# EMU.net
KiCad netlist of a schematic drawn in Altium Designer
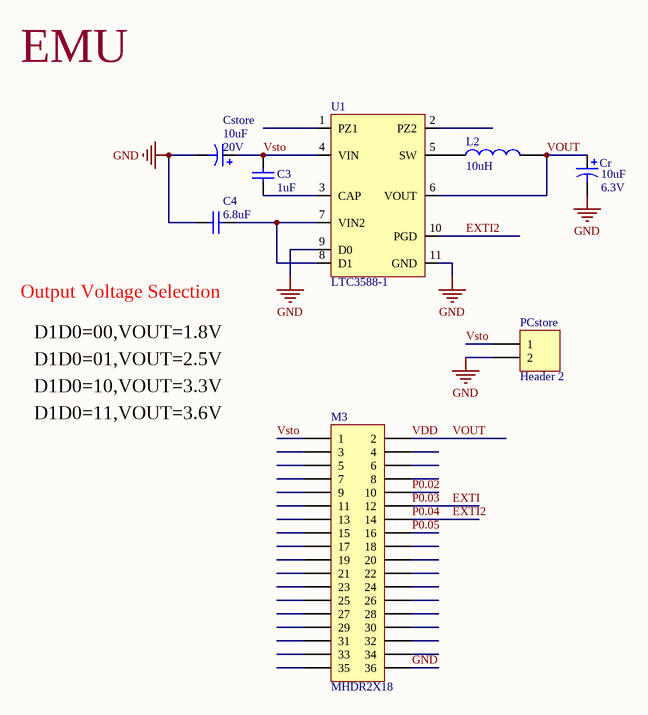
[diagram p0: EMU.SchDoc]

(export (version "E")
  (design (tool "Eeschema 10.0.6"))
  (components
    (comp (ref "C3")
      (value "1uF")
      (footprint "6-0805_N")
      (description "Capacitor")
      (fields (field (name "Comment") "CAP") (field (name "PUBLISHER") "Altium Limited"))
      (libsource (lib "Harry_PCBLib") (part "Cap"))
    )
    (comp (ref "C4")
      (value "6.8uF")
      (footprint "6-0805_N")
      (description "Capacitor")
      (fields (field (name "Comment") "CAP") (field (name "PUBLISHER") "Altium Limited"))
      (libsource (lib "Harry_PCBLib") (part "Cap"))
    )
    (comp (ref "Cr")
      (value "6.3V")
      (footprint "3216[1206]")
      (description "Polarized Capacitor (Radial)")
      (fields (field (name "ALTIUM_VALUE") "10uF") (field (name "PUBLISHER") "Altium Limited"))
      (libsource (lib "Miscellaneous Devices") (part "Cap Pol1"))
    )
    (comp (ref "Cstore")
      (value "10uF")
      (footprint "钽电容")
      (description "Polarized Capacitor (Radial)")
      (fields
        (field (name "NOMINAL VOLTAGE") "20V")
        (field (name "Comment") "Cap Pol1")
        (field (name "PUBLISHER") "Altium Limited")
      )
      (libsource (lib "Miscellaneous Devices") (part "Cap Pol1"))
    )
    (comp (ref "L2") (value "10uH") (footprint "1812") (libsource (lib "Harry_PCBLib") (part "INDUCTOR")))
    (comp (ref "M3")
      (value "MHDR2X18")
      (footprint "header:module9x4")
      (description "Header, 18-Pin, Dual row")
      (fields (field (name "PUBLISHER") "Altium Limited"))
      (libsource (lib "Miscellaneous Connectors") (part "MHDR2X18"))
    )
    (comp (ref "PCstore")
      (value "Header 2")
      (footprint "HDR1X2")
      (description "Header, 2-Pin")
      (fields (field (name "PUBLISHER") "Altium Limited"))
      (libsource (lib "Miscellaneous Connectors") (part "Header 2"))
    )
    (comp (ref "U1")
      (value "LTC3588-1")
      (footprint "LTC 3588-1")
      (description "Nanopower energy harvesting power supply")
      (libsource (lib "Self-power SSHI") (part "LTC3588-1"))
    )
  )
  (nets
    (net (code "1") (name "/EXTI") (class "Default")
      (node (ref "M3") (pin "12") (pinfunction "12_12") (pintype "passive"))
    )
    (net (code "2") (name "/EXTI2") (class "Default")
      (node (ref "M3") (pin "14") (pinfunction "14_14") (pintype "passive"))
      (node (ref "U1") (pin "10") (pinfunction "PGD_10") (pintype "passive"))
    )
    (net (code "3") (name "/P0.02") (class "Default")
      (node (ref "M3") (pin "10") (pinfunction "10_10") (pintype "passive"))
    )
    (net (code "4") (name "/P0.05") (class "Default")
      (node (ref "M3") (pin "16") (pinfunction "16_16") (pintype "passive"))
    )
    (net (code "5") (name "/VDD") (class "Default")
      (node (ref "Cr") (pin "1") (pinfunction "1_1") (pintype "passive"))
      (node (ref "L2") (pin "2") (pinfunction "2_2") (pintype "passive"))
      (node (ref "M3") (pin "2") (pinfunction "2_2") (pintype "passive"))
      (node (ref "U1") (pin "6") (pinfunction "VOUT_6") (pintype "passive"))
    )
    (net (code "6") (name "/Vsto") (class "Default")
      (node (ref "C3") (pin "2") (pinfunction "2_2") (pintype "passive"))
      (node (ref "Cstore") (pin "1") (pinfunction "1_1") (pintype "passive"))
      (node (ref "M3") (pin "1") (pinfunction "1_1") (pintype "passive"))
      (node (ref "PCstore") (pin "1") (pinfunction "1_1") (pintype "passive"))
      (node (ref "U1") (pin "4") (pinfunction "VIN_4") (pintype "passive"))
    )
    (net (code "7") (name "GND") (class "Default")
      (node (ref "C4") (pin "2") (pinfunction "2_2") (pintype "passive"))
      (node (ref "Cr") (pin "2") (pinfunction "2_2") (pintype "passive"))
      (node (ref "Cstore") (pin "2") (pinfunction "2_2") (pintype "passive"))
      (node (ref "M3") (pin "36") (pinfunction "36_36") (pintype "passive"))
      (node (ref "PCstore") (pin "2") (pinfunction "2_2") (pintype "passive"))
      (node (ref "U1") (pin "11") (pinfunction "GND_11") (pintype "passive"))
      (node (ref "U1") (pin "9") (pinfunction "D0_9") (pintype "passive"))
    )
    (net (code "8") (name "Net-(U1-CAP)") (class "Default")
      (node (ref "C3") (pin "1") (pinfunction "1_1") (pintype "passive"))
      (node (ref "U1") (pin "3") (pinfunction "CAP_3") (pintype "passive"))
    )
    (net (code "9") (name "Net-(U1-D1)") (class "Default")
      (node (ref "C4") (pin "1") (pinfunction "1_1") (pintype "passive"))
      (node (ref "U1") (pin "7") (pinfunction "VIN2_7") (pintype "passive"))
      (node (ref "U1") (pin "8") (pinfunction "D1_8") (pintype "passive"))
    )
    (net (code "10") (name "Net-(U1-SW)") (class "Default")
      (node (ref "L2") (pin "1") (pinfunction "1_1") (pintype "passive"))
      (node (ref "U1") (pin "5") (pinfunction "SW_5") (pintype "passive"))
    )
    (net (code "11") (name "unconnected-(M3-Pad3)") (class "Default")
      (node (ref "M3") (pin "3") (pinfunction "3_3") (pintype "passive"))
    )
    (net (code "12") (name "unconnected-(M3-Pad4)") (class "Default")
      (node (ref "M3") (pin "4") (pinfunction "4_4") (pintype "passive"))
    )
    (net (code "13") (name "unconnected-(M3-Pad5)") (class "Default")
      (node (ref "M3") (pin "5") (pinfunction "5_5") (pintype "passive"))
    )
    (net (code "14") (name "unconnected-(M3-Pad6)") (class "Default")
      (node (ref "M3") (pin "6") (pinfunction "6_6") (pintype "passive"))
    )
    (net (code "15") (name "unconnected-(M3-Pad7)") (class "Default")
      (node (ref "M3") (pin "7") (pinfunction "7_7") (pintype "passive"))
    )
    (net (code "16") (name "unconnected-(M3-Pad8)") (class "Default")
      (node (ref "M3") (pin "8") (pinfunction "8_8") (pintype "passive"))
    )
    (net (code "17") (name "unconnected-(M3-Pad9)") (class "Default")
      (node (ref "M3") (pin "9") (pinfunction "9_9") (pintype "passive"))
    )
    (net (code "18") (name "unconnected-(M3-Pad11)") (class "Default")
      (node (ref "M3") (pin "11") (pinfunction "11_11") (pintype "passive"))
    )
    (net (code "19") (name "unconnected-(M3-Pad13)") (class "Default")
      (node (ref "M3") (pin "13") (pinfunction "13_13") (pintype "passive"))
    )
    (net (code "20") (name "unconnected-(M3-Pad15)") (class "Default")
      (node (ref "M3") (pin "15") (pinfunction "15_15") (pintype "passive"))
    )
    (net (code "21") (name "unconnected-(M3-Pad17)") (class "Default")
      (node (ref "M3") (pin "17") (pinfunction "17_17") (pintype "passive"))
    )
    (net (code "22") (name "unconnected-(M3-Pad18)") (class "Default")
      (node (ref "M3") (pin "18") (pinfunction "18_18") (pintype "passive"))
    )
    (net (code "23") (name "unconnected-(M3-Pad19)") (class "Default")
      (node (ref "M3") (pin "19") (pinfunction "19_19") (pintype "passive"))
    )
    (net (code "24") (name "unconnected-(M3-Pad20)") (class "Default")
      (node (ref "M3") (pin "20") (pinfunction "20_20") (pintype "passive"))
    )
    (net (code "25") (name "unconnected-(M3-Pad21)") (class "Default")
      (node (ref "M3") (pin "21") (pinfunction "21_21") (pintype "passive"))
    )
    (net (code "26") (name "unconnected-(M3-Pad22)") (class "Default")
      (node (ref "M3") (pin "22") (pinfunction "22_22") (pintype "passive"))
    )
    (net (code "27") (name "unconnected-(M3-Pad23)") (class "Default")
      (node (ref "M3") (pin "23") (pinfunction "23_23") (pintype "passive"))
    )
    (net (code "28") (name "unconnected-(M3-Pad24)") (class "Default")
      (node (ref "M3") (pin "24") (pinfunction "24_24") (pintype "passive"))
    )
    (net (code "29") (name "unconnected-(M3-Pad25)") (class "Default")
      (node (ref "M3") (pin "25") (pinfunction "25_25") (pintype "passive"))
    )
    (net (code "30") (name "unconnected-(M3-Pad26)") (class "Default")
      (node (ref "M3") (pin "26") (pinfunction "26_26") (pintype "passive"))
    )
    (net (code "31") (name "unconnected-(M3-Pad27)") (class "Default")
      (node (ref "M3") (pin "27") (pinfunction "27_27") (pintype "passive"))
    )
    (net (code "32") (name "unconnected-(M3-Pad28)") (class "Default")
      (node (ref "M3") (pin "28") (pinfunction "28_28") (pintype "passive"))
    )
    (net (code "33") (name "unconnected-(M3-Pad29)") (class "Default")
      (node (ref "M3") (pin "29") (pinfunction "29_29") (pintype "passive"))
    )
    (net (code "34") (name "unconnected-(M3-Pad30)") (class "Default")
      (node (ref "M3") (pin "30") (pinfunction "30_30") (pintype "passive"))
    )
    (net (code "35") (name "unconnected-(M3-Pad31)") (class "Default")
      (node (ref "M3") (pin "31") (pinfunction "31_31") (pintype "passive"))
    )
    (net (code "36") (name "unconnected-(M3-Pad32)") (class "Default")
      (node (ref "M3") (pin "32") (pinfunction "32_32") (pintype "passive"))
    )
    (net (code "37") (name "unconnected-(M3-Pad33)") (class "Default")
      (node (ref "M3") (pin "33") (pinfunction "33_33") (pintype "passive"))
    )
    (net (code "38") (name "unconnected-(M3-Pad34)") (class "Default")
      (node (ref "M3") (pin "34") (pinfunction "34_34") (pintype "passive"))
    )
    (net (code "39") (name "unconnected-(M3-Pad35)") (class "Default")
      (node (ref "M3") (pin "35") (pinfunction "35_35") (pintype "passive"))
    )
    (net (code "40") (name "unconnected-(U1-PZ1-Pad1)") (class "Default")
      (node (ref "U1") (pin "1") (pinfunction "PZ1_1") (pintype "passive"))
    )
    (net (code "41") (name "unconnected-(U1-PZ2-Pad2)") (class "Default")
      (node (ref "U1") (pin "2") (pinfunction "PZ2_2") (pintype "passive"))
    )
  )
)
